# D1_-_LCD_TH_Screws.net
KiCad netlist of a schematic drawn in EAGLE
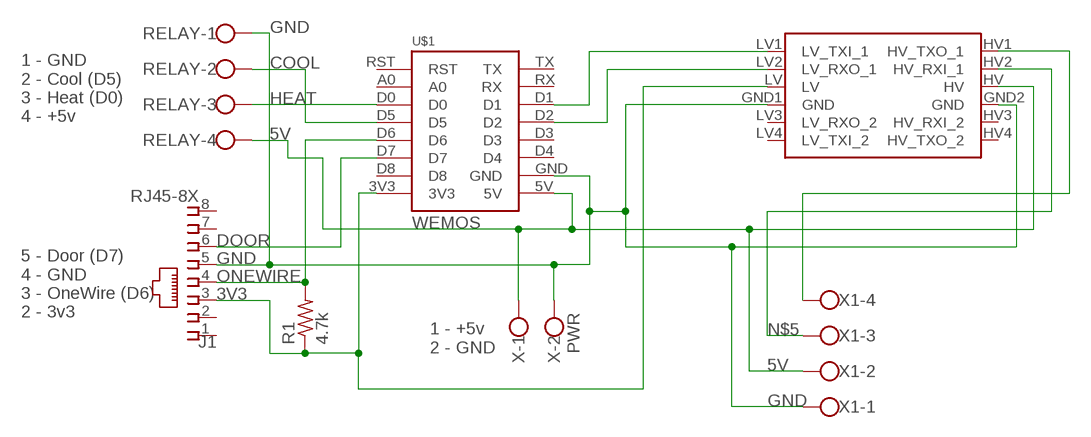
[diagram p0: schematic, sheet 1]

(export (version "E")
  (design (tool "Eeschema 10.0.6"))
  (components
    (comp (ref "J1")
      (value "RJ45-8X")
      (footprint "eagle-import:RJ45-NO-SHIELD")
      (libsource (lib "eagle-import") (part "RJ45-8X"))
    )
    (comp (ref "R1")
      (value "4.7k")
      (footprint "eagle-import:0309_12")
      (libsource (lib "eagle-import") (part "R-US_0309/12"))
    )
    (comp (ref "RELAY")
      (value "W237-4")
      (footprint "eagle-import:W237-4")
      (libsource (lib "eagle-import") (part "W237-4"))
    )
    (comp (ref "U$1")
      (value "WEMOS")
      (footprint "eagle-import:WEMOS")
      (libsource (lib "eagle-import") (part "WEMOS"))
    )
    (comp (ref "U$3")
      (value "SPARKFUN_LOGIC_LEVEL_CONVERTER")
      (footprint "eagle-import:SPARKFUN_LOGIC_LEVEL_CONVERTER")
      (libsource (lib "eagle-import") (part "SPARKFUN_LOGIC_LEVEL_CONVERTER"))
    )
    (comp (ref "X")
      (value "PWR")
      (footprint "eagle-import:W237-102")
      (fields (field (name "MPN") "237-102"))
      (libsource (lib "eagle-import") (part "W237-102"))
    )
    (comp (ref "X1")
      (value "W237-4")
      (footprint "eagle-import:W237-4")
      (libsource (lib "eagle-import") (part "W237-4"))
    )
  )
  (nets
    (net (code "1") (name "/3V3") (class "Default")
      (node (ref "J1") (pin "3") (pinfunction "3_3") (pintype "passive"))
      (node (ref "R1") (pin "1") (pinfunction "1_1") (pintype "passive"))
      (node (ref "U$1") (pin "3V3") (pinfunction "3V3_3V3") (pintype "bidirectional"))
      (node (ref "U$3") (pin "LV") (pinfunction "LV_LV") (pintype "power_in"))
    )
    (net (code "2") (name "/5V") (class "Default")
      (node (ref "RELAY") (pin "4") (pinfunction "KL_4") (pintype "passive"))
      (node (ref "U$1") (pin "5V") (pinfunction "5V_5V") (pintype "bidirectional"))
      (node (ref "U$3") (pin "HV") (pinfunction "HV_HV") (pintype "power_in"))
      (node (ref "X") (pin "1") (pinfunction "KL_1") (pintype "passive"))
      (node (ref "X1") (pin "2") (pinfunction "KL_2") (pintype "passive"))
    )
    (net (code "3") (name "/COOL") (class "Default")
      (node (ref "RELAY") (pin "2") (pinfunction "KL_2") (pintype "passive"))
      (node (ref "U$1") (pin "D5") (pinfunction "D5_D5") (pintype "bidirectional"))
    )
    (net (code "4") (name "/DOOR") (class "Default")
      (node (ref "J1") (pin "6") (pinfunction "6_6") (pintype "passive"))
      (node (ref "U$1") (pin "D7") (pinfunction "D7_D7") (pintype "bidirectional"))
    )
    (net (code "5") (name "/GND") (class "Default")
      (node (ref "J1") (pin "5") (pinfunction "5_5") (pintype "passive"))
      (node (ref "RELAY") (pin "1") (pinfunction "KL_1") (pintype "passive"))
      (node (ref "U$1") (pin "GND") (pinfunction "GND_GND") (pintype "bidirectional"))
      (node (ref "U$3") (pin "GND1") (pinfunction "GND_GND1") (pintype "power_in"))
      (node (ref "U$3") (pin "GND2") (pinfunction "GND_GND2") (pintype "power_in"))
      (node (ref "X") (pin "2") (pinfunction "KL_2") (pintype "passive"))
      (node (ref "X1") (pin "1") (pinfunction "KL_1") (pintype "passive"))
    )
    (net (code "6") (name "/HEAT") (class "Default")
      (node (ref "RELAY") (pin "3") (pinfunction "KL_3") (pintype "passive"))
      (node (ref "U$1") (pin "D0") (pinfunction "D0_D0") (pintype "bidirectional"))
    )
    (net (code "7") (name "/N$5") (class "Default")
      (node (ref "U$3") (pin "HV2") (pinfunction "HV_RXI_1_HV2") (pintype "bidirectional"))
      (node (ref "X1") (pin "3") (pinfunction "KL_3") (pintype "passive"))
    )
    (net (code "8") (name "/ONEWIRE") (class "Default")
      (node (ref "J1") (pin "4") (pinfunction "4_4") (pintype "passive"))
      (node (ref "R1") (pin "2") (pinfunction "2_2") (pintype "passive"))
      (node (ref "U$1") (pin "D6") (pinfunction "D6_D6") (pintype "bidirectional"))
    )
    (net (code "9") (name "Net-(U$3-HV_TXO_1)") (class "Default")
      (node (ref "U$3") (pin "HV1") (pinfunction "HV_TXO_1_HV1") (pintype "bidirectional"))
      (node (ref "X1") (pin "4") (pinfunction "KL_4") (pintype "passive"))
    )
    (net (code "10") (name "Net-(U$3-LV_RXO_1)") (class "Default")
      (node (ref "U$1") (pin "D2") (pinfunction "D2_D2") (pintype "bidirectional"))
      (node (ref "U$3") (pin "LV2") (pinfunction "LV_RXO_1_LV2") (pintype "bidirectional"))
    )
    (net (code "11") (name "Net-(U$3-LV_TXI_1)") (class "Default")
      (node (ref "U$1") (pin "D1") (pinfunction "D1_D1") (pintype "bidirectional"))
      (node (ref "U$3") (pin "LV1") (pinfunction "LV_TXI_1_LV1") (pintype "bidirectional"))
    )
    (net (code "12") (name "unconnected-(J1-Pad1)") (class "Default")
      (node (ref "J1") (pin "1") (pinfunction "1_1") (pintype "passive"))
    )
    (net (code "13") (name "unconnected-(J1-Pad2)") (class "Default")
      (node (ref "J1") (pin "2") (pinfunction "2_2") (pintype "passive"))
    )
    (net (code "14") (name "unconnected-(J1-Pad7)") (class "Default")
      (node (ref "J1") (pin "7") (pinfunction "7_7") (pintype "passive"))
    )
    (net (code "15") (name "unconnected-(J1-Pad8)") (class "Default")
      (node (ref "J1") (pin "8") (pinfunction "8_8") (pintype "passive"))
    )
    (net (code "16") (name "unconnected-(U$1-PadA0)") (class "Default")
      (node (ref "U$1") (pin "A0") (pinfunction "A0_A0") (pintype "bidirectional"))
    )
    (net (code "17") (name "unconnected-(U$1-PadD3)") (class "Default")
      (node (ref "U$1") (pin "D3") (pinfunction "D3_D3") (pintype "bidirectional"))
    )
    (net (code "18") (name "unconnected-(U$1-PadD4)") (class "Default")
      (node (ref "U$1") (pin "D4") (pinfunction "D4_D4") (pintype "bidirectional"))
    )
    (net (code "19") (name "unconnected-(U$1-PadD8)") (class "Default")
      (node (ref "U$1") (pin "D8") (pinfunction "D8_D8") (pintype "bidirectional"))
    )
    (net (code "20") (name "unconnected-(U$1-PadRST)") (class "Default")
      (node (ref "U$1") (pin "RST") (pinfunction "RST_RST") (pintype "bidirectional"))
    )
    (net (code "21") (name "unconnected-(U$1-PadRX)") (class "Default")
      (node (ref "U$1") (pin "RX") (pinfunction "RX_RX") (pintype "bidirectional"))
    )
    (net (code "22") (name "unconnected-(U$1-PadTX)") (class "Default")
      (node (ref "U$1") (pin "TX") (pinfunction "TX_TX") (pintype "bidirectional"))
    )
    (net (code "23") (name "unconnected-(U$3-HV_RXI_2-PadHV3)") (class "Default")
      (node (ref "U$3") (pin "HV3") (pinfunction "HV_RXI_2_HV3") (pintype "bidirectional"))
    )
    (net (code "24") (name "unconnected-(U$3-HV_TXO_2-PadHV4)") (class "Default")
      (node (ref "U$3") (pin "HV4") (pinfunction "HV_TXO_2_HV4") (pintype "bidirectional"))
    )
    (net (code "25") (name "unconnected-(U$3-LV_RXO_2-PadLV3)") (class "Default")
      (node (ref "U$3") (pin "LV3") (pinfunction "LV_RXO_2_LV3") (pintype "bidirectional"))
    )
    (net (code "26") (name "unconnected-(U$3-LV_TXI_2-PadLV4)") (class "Default")
      (node (ref "U$3") (pin "LV4") (pinfunction "LV_TXI_2_LV4") (pintype "bidirectional"))
    )
  )
)
